# mpc57_cpuio1.net
KiCad netlist of a schematic drawn in Altium Designer
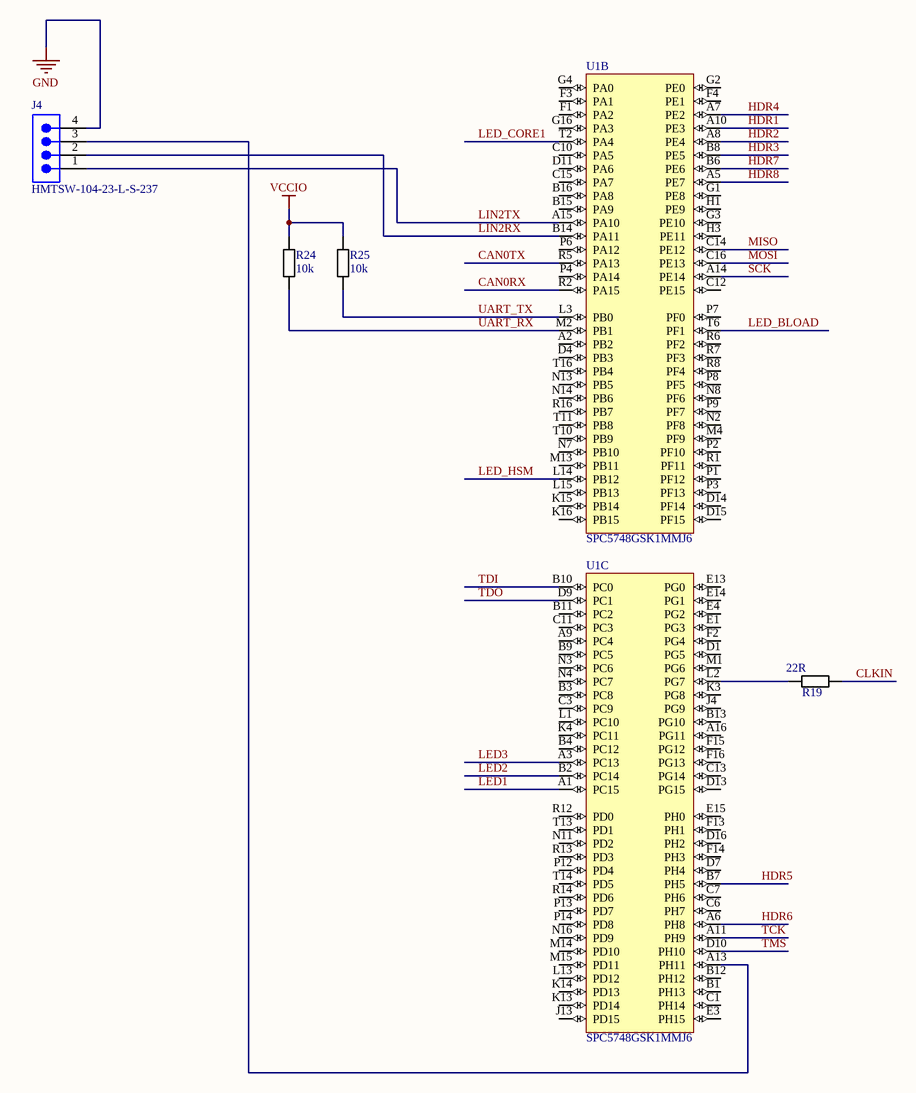
[diagram p0: mpc57_cpuio1.SchDoc]

(export (version "E")
  (design (tool "Eeschema 10.0.6"))
  (components
    (comp (ref "J4")
      (value "HMTSW-104-23-L-S-237")
      (footprint "SMTC-HMTSW-104-23-X-S-237")
      (fields (field (name "MANUFACTURER") "Samtec"))
      (libsource (lib "Altium Content Vault") (part "CMP-1024-00020-1"))
    )
    (comp (ref "R19")
      (value "22R")
      (footprint "RESC1608X55N")
      (description "22R res, 0603, 1%, 1/10W")
      (fields (field (name "PART NUMBER") "RCHIP-22R-0603") (field (name "TOLERANCE") "1%"))
      (libsource (lib "") (part "RES-EU_1"))
    )
    (comp (ref "R24")
      (value "10k")
      (footprint "RESC1608X55N")
      (description "10k res, 0603, 1%, 1/10W")
      (fields (field (name "PART NUMBER") "RCHIP-10K-0603") (field (name "TOLERANCE") "1%"))
      (libsource (lib "NewAE_AltiumLib") (part "RES-EU"))
    )
    (comp (ref "R25")
      (value "10k")
      (footprint "RESC1608X55N")
      (description "10k res, 0603, 1%, 1/10W")
      (fields (field (name "PART NUMBER") "RCHIP-10K-0603") (field (name "TOLERANCE") "1%"))
      (libsource (lib "NewAE_AltiumLib") (part "RES-EU"))
    )
    (comp (ref "U1")
      (value "SPC5748GSK1MMJ6")
      (footprint "NewAE_AltiumLib:BGA256C100P16X16_1700X1700X170")
      (description "Freescale 32-bit MCU, Triple core, 6MB Flash, 160MHz, -40/+125degC, Automotive Qualified, BGA 256")
      (libsource (lib "NewAE_AltiumLib") (part "SPC5748GSK1MMJ6"))
    )
  )
  (nets
    (net (code "1") (name "/CAN0RX") (class "Default")
      (node (ref "U1") (pin "R2") (pinfunction "PA15_R2") (pintype "bidirectional"))
    )
    (net (code "2") (name "/CAN0TX") (class "Default")
      (node (ref "U1") (pin "R5") (pinfunction "PA13_R5") (pintype "bidirectional"))
    )
    (net (code "3") (name "/CLKIN") (class "Default")
      (node (ref "R19") (pin "2") (pinfunction "2_2") (pintype "passive"))
    )
    (net (code "4") (name "/HDR1") (class "Default")
      (node (ref "U1") (pin "A10") (pinfunction "PE3_A10") (pintype "bidirectional"))
    )
    (net (code "5") (name "/HDR2") (class "Default")
      (node (ref "U1") (pin "A8") (pinfunction "PE4_A8") (pintype "bidirectional"))
    )
    (net (code "6") (name "/HDR3") (class "Default")
      (node (ref "U1") (pin "B8") (pinfunction "PE5_B8") (pintype "bidirectional"))
    )
    (net (code "7") (name "/HDR4") (class "Default")
      (node (ref "U1") (pin "A7") (pinfunction "PE2_A7") (pintype "bidirectional"))
    )
    (net (code "8") (name "/HDR5") (class "Default")
      (node (ref "U1") (pin "B7") (pinfunction "PH5_B7") (pintype "bidirectional"))
    )
    (net (code "9") (name "/HDR6") (class "Default")
      (node (ref "U1") (pin "A6") (pinfunction "PH8_A6") (pintype "bidirectional"))
    )
    (net (code "10") (name "/HDR7") (class "Default")
      (node (ref "U1") (pin "B6") (pinfunction "PE6_B6") (pintype "bidirectional"))
    )
    (net (code "11") (name "/HDR8") (class "Default")
      (node (ref "U1") (pin "A5") (pinfunction "PE7_A5") (pintype "bidirectional"))
    )
    (net (code "12") (name "/LED1") (class "Default")
      (node (ref "U1") (pin "A1") (pinfunction "PC15_A1") (pintype "bidirectional"))
    )
    (net (code "13") (name "/LED2") (class "Default")
      (node (ref "U1") (pin "B2") (pinfunction "PC14_B2") (pintype "bidirectional"))
    )
    (net (code "14") (name "/LED3") (class "Default")
      (node (ref "U1") (pin "A3") (pinfunction "PC13_A3") (pintype "bidirectional"))
    )
    (net (code "15") (name "/LED_BLOAD") (class "Default")
      (node (ref "U1") (pin "T6") (pinfunction "PF1_T6") (pintype "bidirectional"))
    )
    (net (code "16") (name "/LED_CORE1") (class "Default")
      (node (ref "U1") (pin "T2") (pinfunction "PA4_T2") (pintype "bidirectional"))
    )
    (net (code "17") (name "/LED_HSM") (class "Default")
      (node (ref "U1") (pin "L14") (pinfunction "PB12_L14") (pintype "bidirectional"))
    )
    (net (code "18") (name "/LIN2RX") (class "Default")
      (node (ref "J4") (pin "2") (pinfunction "2_2") (pintype "passive"))
      (node (ref "U1") (pin "B14") (pinfunction "PA11_B14") (pintype "bidirectional"))
    )
    (net (code "19") (name "/LIN2TX") (class "Default")
      (node (ref "J4") (pin "1") (pinfunction "1_1") (pintype "passive"))
      (node (ref "U1") (pin "A15") (pinfunction "PA10_A15") (pintype "bidirectional"))
    )
    (net (code "20") (name "/MISO") (class "Default")
      (node (ref "U1") (pin "C14") (pinfunction "PE12_C14") (pintype "bidirectional"))
    )
    (net (code "21") (name "/MOSI") (class "Default")
      (node (ref "U1") (pin "C16") (pinfunction "PE13_C16") (pintype "bidirectional"))
    )
    (net (code "22") (name "/SCK") (class "Default")
      (node (ref "U1") (pin "A14") (pinfunction "PE14_A14") (pintype "bidirectional"))
    )
    (net (code "23") (name "/TCK") (class "Default")
      (node (ref "U1") (pin "A11") (pinfunction "PH9_A11") (pintype "bidirectional"))
    )
    (net (code "24") (name "/TDI") (class "Default")
      (node (ref "U1") (pin "B10") (pinfunction "PC0_B10") (pintype "bidirectional"))
    )
    (net (code "25") (name "/TDO") (class "Default")
      (node (ref "U1") (pin "D9") (pinfunction "PC1_D9") (pintype "bidirectional"))
    )
    (net (code "26") (name "/TMS") (class "Default")
      (node (ref "U1") (pin "D10") (pinfunction "PH10_D10") (pintype "bidirectional"))
    )
    (net (code "27") (name "/UART_RX") (class "Default")
      (node (ref "R24") (pin "2") (pinfunction "2_2") (pintype "passive"))
      (node (ref "U1") (pin "M2") (pinfunction "PB1_M2") (pintype "bidirectional"))
    )
    (net (code "28") (name "/UART_TX") (class "Default")
      (node (ref "R25") (pin "2") (pinfunction "2_2") (pintype "passive"))
      (node (ref "U1") (pin "L3") (pinfunction "PB0_L3") (pintype "bidirectional"))
    )
    (net (code "29") (name "GND") (class "Default")
      (node (ref "J4") (pin "4") (pinfunction "4_4") (pintype "passive"))
    )
    (net (code "30") (name "Net-(U1C-PG7)") (class "Default")
      (node (ref "R19") (pin "1") (pinfunction "1_1") (pintype "passive"))
      (node (ref "U1") (pin "L2") (pinfunction "PG7_L2") (pintype "bidirectional"))
    )
    (net (code "31") (name "Net-(U1C-PH11)") (class "Default")
      (node (ref "J4") (pin "3") (pinfunction "3_3") (pintype "passive"))
      (node (ref "U1") (pin "A13") (pinfunction "PH11_A13") (pintype "bidirectional"))
    )
    (net (code "32") (name "VCCIO") (class "Default")
      (node (ref "R24") (pin "1") (pinfunction "1_1") (pintype "passive"))
      (node (ref "R25") (pin "1") (pinfunction "1_1") (pintype "passive"))
    )
    (net (code "33") (name "unconnected-(U1B-PA0-PadG4)") (class "Default")
      (node (ref "U1") (pin "G4") (pinfunction "PA0_G4") (pintype "bidirectional"))
    )
    (net (code "34") (name "unconnected-(U1B-PA1-PadF3)") (class "Default")
      (node (ref "U1") (pin "F3") (pinfunction "PA1_F3") (pintype "bidirectional"))
    )
    (net (code "35") (name "unconnected-(U1B-PA2-PadF1)") (class "Default")
      (node (ref "U1") (pin "F1") (pinfunction "PA2_F1") (pintype "bidirectional"))
    )
    (net (code "36") (name "unconnected-(U1B-PA3-PadG16)") (class "Default")
      (node (ref "U1") (pin "G16") (pinfunction "PA3_G16") (pintype "bidirectional"))
    )
    (net (code "37") (name "unconnected-(U1B-PA5-PadC10)") (class "Default")
      (node (ref "U1") (pin "C10") (pinfunction "PA5_C10") (pintype "bidirectional"))
    )
    (net (code "38") (name "unconnected-(U1B-PA6-PadD11)") (class "Default")
      (node (ref "U1") (pin "D11") (pinfunction "PA6_D11") (pintype "bidirectional"))
    )
    (net (code "39") (name "unconnected-(U1B-PA7-PadC15)") (class "Default")
      (node (ref "U1") (pin "C15") (pinfunction "PA7_C15") (pintype "bidirectional"))
    )
    (net (code "40") (name "unconnected-(U1B-PA8-PadB16)") (class "Default")
      (node (ref "U1") (pin "B16") (pinfunction "PA8_B16") (pintype "bidirectional"))
    )
    (net (code "41") (name "unconnected-(U1B-PA9-PadB15)") (class "Default")
      (node (ref "U1") (pin "B15") (pinfunction "PA9_B15") (pintype "bidirectional"))
    )
    (net (code "42") (name "unconnected-(U1B-PA12-PadP6)") (class "Default")
      (node (ref "U1") (pin "P6") (pinfunction "PA12_P6") (pintype "bidirectional"))
    )
    (net (code "43") (name "unconnected-(U1B-PA14-PadP4)") (class "Default")
      (node (ref "U1") (pin "P4") (pinfunction "PA14_P4") (pintype "bidirectional"))
    )
    (net (code "44") (name "unconnected-(U1B-PB2-PadA2)") (class "Default")
      (node (ref "U1") (pin "A2") (pinfunction "PB2_A2") (pintype "bidirectional"))
    )
    (net (code "45") (name "unconnected-(U1B-PB3-PadD4)") (class "Default")
      (node (ref "U1") (pin "D4") (pinfunction "PB3_D4") (pintype "bidirectional"))
    )
    (net (code "46") (name "unconnected-(U1B-PB4-PadT16)") (class "Default")
      (node (ref "U1") (pin "T16") (pinfunction "PB4_T16") (pintype "bidirectional"))
    )
    (net (code "47") (name "unconnected-(U1B-PB5-PadN13)") (class "Default")
      (node (ref "U1") (pin "N13") (pinfunction "PB5_N13") (pintype "bidirectional"))
    )
    (net (code "48") (name "unconnected-(U1B-PB6-PadN14)") (class "Default")
      (node (ref "U1") (pin "N14") (pinfunction "PB6_N14") (pintype "bidirectional"))
    )
    (net (code "49") (name "unconnected-(U1B-PB7-PadR16)") (class "Default")
      (node (ref "U1") (pin "R16") (pinfunction "PB7_R16") (pintype "bidirectional"))
    )
    (net (code "50") (name "unconnected-(U1B-PB8-PadT11)") (class "Default")
      (node (ref "U1") (pin "T11") (pinfunction "PB8_T11") (pintype "bidirectional"))
    )
    (net (code "51") (name "unconnected-(U1B-PB9-PadT10)") (class "Default")
      (node (ref "U1") (pin "T10") (pinfunction "PB9_T10") (pintype "bidirectional"))
    )
    (net (code "52") (name "unconnected-(U1B-PB10-PadN7)") (class "Default")
      (node (ref "U1") (pin "N7") (pinfunction "PB10_N7") (pintype "bidirectional"))
    )
    (net (code "53") (name "unconnected-(U1B-PB11-PadM13)") (class "Default")
      (node (ref "U1") (pin "M13") (pinfunction "PB11_M13") (pintype "bidirectional"))
    )
    (net (code "54") (name "unconnected-(U1B-PB13-PadL15)") (class "Default")
      (node (ref "U1") (pin "L15") (pinfunction "PB13_L15") (pintype "bidirectional"))
    )
    (net (code "55") (name "unconnected-(U1B-PB14-PadK15)") (class "Default")
      (node (ref "U1") (pin "K15") (pinfunction "PB14_K15") (pintype "bidirectional"))
    )
    (net (code "56") (name "unconnected-(U1B-PB15-PadK16)") (class "Default")
      (node (ref "U1") (pin "K16") (pinfunction "PB15_K16") (pintype "bidirectional"))
    )
    (net (code "57") (name "unconnected-(U1B-PE0-PadG2)") (class "Default")
      (node (ref "U1") (pin "G2") (pinfunction "PE0_G2") (pintype "bidirectional"))
    )
    (net (code "58") (name "unconnected-(U1B-PE1-PadF4)") (class "Default")
      (node (ref "U1") (pin "F4") (pinfunction "PE1_F4") (pintype "bidirectional"))
    )
    (net (code "59") (name "unconnected-(U1B-PE8-PadG1)") (class "Default")
      (node (ref "U1") (pin "G1") (pinfunction "PE8_G1") (pintype "bidirectional"))
    )
    (net (code "60") (name "unconnected-(U1B-PE9-PadH1)") (class "Default")
      (node (ref "U1") (pin "H1") (pinfunction "PE9_H1") (pintype "bidirectional"))
    )
    (net (code "61") (name "unconnected-(U1B-PE10-PadG3)") (class "Default")
      (node (ref "U1") (pin "G3") (pinfunction "PE10_G3") (pintype "bidirectional"))
    )
    (net (code "62") (name "unconnected-(U1B-PE11-PadH3)") (class "Default")
      (node (ref "U1") (pin "H3") (pinfunction "PE11_H3") (pintype "bidirectional"))
    )
    (net (code "63") (name "unconnected-(U1B-PE15-PadC12)") (class "Default")
      (node (ref "U1") (pin "C12") (pinfunction "PE15_C12") (pintype "bidirectional"))
    )
    (net (code "64") (name "unconnected-(U1B-PF0-PadP7)") (class "Default")
      (node (ref "U1") (pin "P7") (pinfunction "PF0_P7") (pintype "bidirectional"))
    )
    (net (code "65") (name "unconnected-(U1B-PF2-PadR6)") (class "Default")
      (node (ref "U1") (pin "R6") (pinfunction "PF2_R6") (pintype "bidirectional"))
    )
    (net (code "66") (name "unconnected-(U1B-PF3-PadR7)") (class "Default")
      (node (ref "U1") (pin "R7") (pinfunction "PF3_R7") (pintype "bidirectional"))
    )
    (net (code "67") (name "unconnected-(U1B-PF4-PadR8)") (class "Default")
      (node (ref "U1") (pin "R8") (pinfunction "PF4_R8") (pintype "bidirectional"))
    )
    (net (code "68") (name "unconnected-(U1B-PF5-PadP8)") (class "Default")
      (node (ref "U1") (pin "P8") (pinfunction "PF5_P8") (pintype "bidirectional"))
    )
    (net (code "69") (name "unconnected-(U1B-PF6-PadN8)") (class "Default")
      (node (ref "U1") (pin "N8") (pinfunction "PF6_N8") (pintype "bidirectional"))
    )
    (net (code "70") (name "unconnected-(U1B-PF7-PadP9)") (class "Default")
      (node (ref "U1") (pin "P9") (pinfunction "PF7_P9") (pintype "bidirectional"))
    )
    (net (code "71") (name "unconnected-(U1B-PF8-PadN2)") (class "Default")
      (node (ref "U1") (pin "N2") (pinfunction "PF8_N2") (pintype "bidirectional"))
    )
    (net (code "72") (name "unconnected-(U1B-PF9-PadM4)") (class "Default")
      (node (ref "U1") (pin "M4") (pinfunction "PF9_M4") (pintype "bidirectional"))
    )
    (net (code "73") (name "unconnected-(U1B-PF10-PadP2)") (class "Default")
      (node (ref "U1") (pin "P2") (pinfunction "PF10_P2") (pintype "bidirectional"))
    )
    (net (code "74") (name "unconnected-(U1B-PF11-PadR1)") (class "Default")
      (node (ref "U1") (pin "R1") (pinfunction "PF11_R1") (pintype "bidirectional"))
    )
    (net (code "75") (name "unconnected-(U1B-PF12-PadP1)") (class "Default")
      (node (ref "U1") (pin "P1") (pinfunction "PF12_P1") (pintype "bidirectional"))
    )
    (net (code "76") (name "unconnected-(U1B-PF13-PadP3)") (class "Default")
      (node (ref "U1") (pin "P3") (pinfunction "PF13_P3") (pintype "bidirectional"))
    )
    (net (code "77") (name "unconnected-(U1B-PF14-PadD14)") (class "Default")
      (node (ref "U1") (pin "D14") (pinfunction "PF14_D14") (pintype "bidirectional"))
    )
    (net (code "78") (name "unconnected-(U1B-PF15-PadD15)") (class "Default")
      (node (ref "U1") (pin "D15") (pinfunction "PF15_D15") (pintype "bidirectional"))
    )
    (net (code "79") (name "unconnected-(U1C-PC2-PadB11)") (class "Default")
      (node (ref "U1") (pin "B11") (pinfunction "PC2_B11") (pintype "bidirectional"))
    )
    (net (code "80") (name "unconnected-(U1C-PC3-PadC11)") (class "Default")
      (node (ref "U1") (pin "C11") (pinfunction "PC3_C11") (pintype "bidirectional"))
    )
    (net (code "81") (name "unconnected-(U1C-PC4-PadA9)") (class "Default")
      (node (ref "U1") (pin "A9") (pinfunction "PC4_A9") (pintype "bidirectional"))
    )
    (net (code "82") (name "unconnected-(U1C-PC5-PadB9)") (class "Default")
      (node (ref "U1") (pin "B9") (pinfunction "PC5_B9") (pintype "bidirectional"))
    )
    (net (code "83") (name "unconnected-(U1C-PC6-PadN3)") (class "Default")
      (node (ref "U1") (pin "N3") (pinfunction "PC6_N3") (pintype "bidirectional"))
    )
    (net (code "84") (name "unconnected-(U1C-PC7-PadN4)") (class "Default")
      (node (ref "U1") (pin "N4") (pinfunction "PC7_N4") (pintype "bidirectional"))
    )
    (net (code "85") (name "unconnected-(U1C-PC8-PadB3)") (class "Default")
      (node (ref "U1") (pin "B3") (pinfunction "PC8_B3") (pintype "bidirectional"))
    )
    (net (code "86") (name "unconnected-(U1C-PC9-PadC3)") (class "Default")
      (node (ref "U1") (pin "C3") (pinfunction "PC9_C3") (pintype "bidirectional"))
    )
    (net (code "87") (name "unconnected-(U1C-PC10-PadL1)") (class "Default")
      (node (ref "U1") (pin "L1") (pinfunction "PC10_L1") (pintype "bidirectional"))
    )
    (net (code "88") (name "unconnected-(U1C-PC11-PadK4)") (class "Default")
      (node (ref "U1") (pin "K4") (pinfunction "PC11_K4") (pintype "bidirectional"))
    )
    (net (code "89") (name "unconnected-(U1C-PC12-PadB4)") (class "Default")
      (node (ref "U1") (pin "B4") (pinfunction "PC12_B4") (pintype "bidirectional"))
    )
    (net (code "90") (name "unconnected-(U1C-PD0-PadR12)") (class "Default")
      (node (ref "U1") (pin "R12") (pinfunction "PD0_R12") (pintype "bidirectional"))
    )
    (net (code "91") (name "unconnected-(U1C-PD1-PadT13)") (class "Default")
      (node (ref "U1") (pin "T13") (pinfunction "PD1_T13") (pintype "bidirectional"))
    )
    (net (code "92") (name "unconnected-(U1C-PD2-PadN11)") (class "Default")
      (node (ref "U1") (pin "N11") (pinfunction "PD2_N11") (pintype "bidirectional"))
    )
    (net (code "93") (name "unconnected-(U1C-PD3-PadR13)") (class "Default")
      (node (ref "U1") (pin "R13") (pinfunction "PD3_R13") (pintype "bidirectional"))
    )
    (net (code "94") (name "unconnected-(U1C-PD4-PadP12)") (class "Default")
      (node (ref "U1") (pin "P12") (pinfunction "PD4_P12") (pintype "bidirectional"))
    )
    (net (code "95") (name "unconnected-(U1C-PD5-PadT14)") (class "Default")
      (node (ref "U1") (pin "T14") (pinfunction "PD5_T14") (pintype "bidirectional"))
    )
    (net (code "96") (name "unconnected-(U1C-PD6-PadR14)") (class "Default")
      (node (ref "U1") (pin "R14") (pinfunction "PD6_R14") (pintype "bidirectional"))
    )
    (net (code "97") (name "unconnected-(U1C-PD7-PadP13)") (class "Default")
      (node (ref "U1") (pin "P13") (pinfunction "PD7_P13") (pintype "bidirectional"))
    )
    (net (code "98") (name "unconnected-(U1C-PD8-PadP14)") (class "Default")
      (node (ref "U1") (pin "P14") (pinfunction "PD8_P14") (pintype "bidirectional"))
    )
    (net (code "99") (name "unconnected-(U1C-PD9-PadN16)") (class "Default")
      (node (ref "U1") (pin "N16") (pinfunction "PD9_N16") (pintype "bidirectional"))
    )
    (net (code "100") (name "unconnected-(U1C-PD10-PadM14)") (class "Default")
      (node (ref "U1") (pin "M14") (pinfunction "PD10_M14") (pintype "bidirectional"))
    )
    (net (code "101") (name "unconnected-(U1C-PD11-PadM15)") (class "Default")
      (node (ref "U1") (pin "M15") (pinfunction "PD11_M15") (pintype "bidirectional"))
    )
    (net (code "102") (name "unconnected-(U1C-PD12-PadL13)") (class "Default")
      (node (ref "U1") (pin "L13") (pinfunction "PD12_L13") (pintype "bidirectional"))
    )
    (net (code "103") (name "unconnected-(U1C-PD13-PadK14)") (class "Default")
      (node (ref "U1") (pin "K14") (pinfunction "PD13_K14") (pintype "bidirectional"))
    )
    (net (code "104") (name "unconnected-(U1C-PD14-PadK13)") (class "Default")
      (node (ref "U1") (pin "K13") (pinfunction "PD14_K13") (pintype "bidirectional"))
    )
    (net (code "105") (name "unconnected-(U1C-PD15-PadJ13)") (class "Default")
      (node (ref "U1") (pin "J13") (pinfunction "PD15_J13") (pintype "bidirectional"))
    )
    (net (code "106") (name "unconnected-(U1C-PG0-PadE13)") (class "Default")
      (node (ref "U1") (pin "E13") (pinfunction "PG0_E13") (pintype "bidirectional"))
    )
    (net (code "107") (name "unconnected-(U1C-PG1-PadE14)") (class "Default")
      (node (ref "U1") (pin "E14") (pinfunction "PG1_E14") (pintype "bidirectional"))
    )
    (net (code "108") (name "unconnected-(U1C-PG2-PadE4)") (class "Default")
      (node (ref "U1") (pin "E4") (pinfunction "PG2_E4") (pintype "bidirectional"))
    )
    (net (code "109") (name "unconnected-(U1C-PG3-PadE1)") (class "Default")
      (node (ref "U1") (pin "E1") (pinfunction "PG3_E1") (pintype "bidirectional"))
    )
    (net (code "110") (name "unconnected-(U1C-PG4-PadF2)") (class "Default")
      (node (ref "U1") (pin "F2") (pinfunction "PG4_F2") (pintype "bidirectional"))
    )
    (net (code "111") (name "unconnected-(U1C-PG5-PadD1)") (class "Default")
      (node (ref "U1") (pin "D1") (pinfunction "PG5_D1") (pintype "bidirectional"))
    )
    (net (code "112") (name "unconnected-(U1C-PG6-PadM1)") (class "Default")
      (node (ref "U1") (pin "M1") (pinfunction "PG6_M1") (pintype "bidirectional"))
    )
    (net (code "113") (name "unconnected-(U1C-PG8-PadK3)") (class "Default")
      (node (ref "U1") (pin "K3") (pinfunction "PG8_K3") (pintype "bidirectional"))
    )
    (net (code "114") (name "unconnected-(U1C-PG9-PadJ4)") (class "Default")
      (node (ref "U1") (pin "J4") (pinfunction "PG9_J4") (pintype "bidirectional"))
    )
    (net (code "115") (name "unconnected-(U1C-PG10-PadB13)") (class "Default")
      (node (ref "U1") (pin "B13") (pinfunction "PG10_B13") (pintype "bidirectional"))
    )
    (net (code "116") (name "unconnected-(U1C-PG11-PadA16)") (class "Default")
      (node (ref "U1") (pin "A16") (pinfunction "PG11_A16") (pintype "bidirectional"))
    )
    (net (code "117") (name "unconnected-(U1C-PG12-PadF15)") (class "Default")
      (node (ref "U1") (pin "F15") (pinfunction "PG12_F15") (pintype "bidirectional"))
    )
    (net (code "118") (name "unconnected-(U1C-PG13-PadF16)") (class "Default")
      (node (ref "U1") (pin "F16") (pinfunction "PG13_F16") (pintype "bidirectional"))
    )
    (net (code "119") (name "unconnected-(U1C-PG14-PadC13)") (class "Default")
      (node (ref "U1") (pin "C13") (pinfunction "PG14_C13") (pintype "bidirectional"))
    )
    (net (code "120") (name "unconnected-(U1C-PG15-PadD13)") (class "Default")
      (node (ref "U1") (pin "D13") (pinfunction "PG15_D13") (pintype "bidirectional"))
    )
    (net (code "121") (name "unconnected-(U1C-PH0-PadE15)") (class "Default")
      (node (ref "U1") (pin "E15") (pinfunction "PH0_E15") (pintype "bidirectional"))
    )
    (net (code "122") (name "unconnected-(U1C-PH1-PadF13)") (class "Default")
      (node (ref "U1") (pin "F13") (pinfunction "PH1_F13") (pintype "bidirectional"))
    )
    (net (code "123") (name "unconnected-(U1C-PH2-PadD16)") (class "Default")
      (node (ref "U1") (pin "D16") (pinfunction "PH2_D16") (pintype "bidirectional"))
    )
    (net (code "124") (name "unconnected-(U1C-PH3-PadF14)") (class "Default")
      (node (ref "U1") (pin "F14") (pinfunction "PH3_F14") (pintype "bidirectional"))
    )
    (net (code "125") (name "unconnected-(U1C-PH4-PadD7)") (class "Default")
      (node (ref "U1") (pin "D7") (pinfunction "PH4_D7") (pintype "bidirectional"))
    )
    (net (code "126") (name "unconnected-(U1C-PH6-PadC7)") (class "Default")
      (node (ref "U1") (pin "C7") (pinfunction "PH6_C7") (pintype "bidirectional"))
    )
    (net (code "127") (name "unconnected-(U1C-PH7-PadC6)") (class "Default")
      (node (ref "U1") (pin "C6") (pinfunction "PH7_C6") (pintype "bidirectional"))
    )
    (net (code "128") (name "unconnected-(U1C-PH12-PadB12)") (class "Default")
      (node (ref "U1") (pin "B12") (pinfunction "PH12_B12") (pintype "bidirectional"))
    )
    (net (code "129") (name "unconnected-(U1C-PH13-PadB1)") (class "Default")
      (node (ref "U1") (pin "B1") (pinfunction "PH13_B1") (pintype "bidirectional"))
    )
    (net (code "130") (name "unconnected-(U1C-PH14-PadC1)") (class "Default")
      (node (ref "U1") (pin "C1") (pinfunction "PH14_C1") (pintype "bidirectional"))
    )
    (net (code "131") (name "unconnected-(U1C-PH15-PadE3)") (class "Default")
      (node (ref "U1") (pin "E3") (pinfunction "PH15_E3") (pintype "bidirectional"))
    )
  )
)
